# Logical_EPS_v_1_0.net
KiCad netlist of a schematic drawn in EAGLE
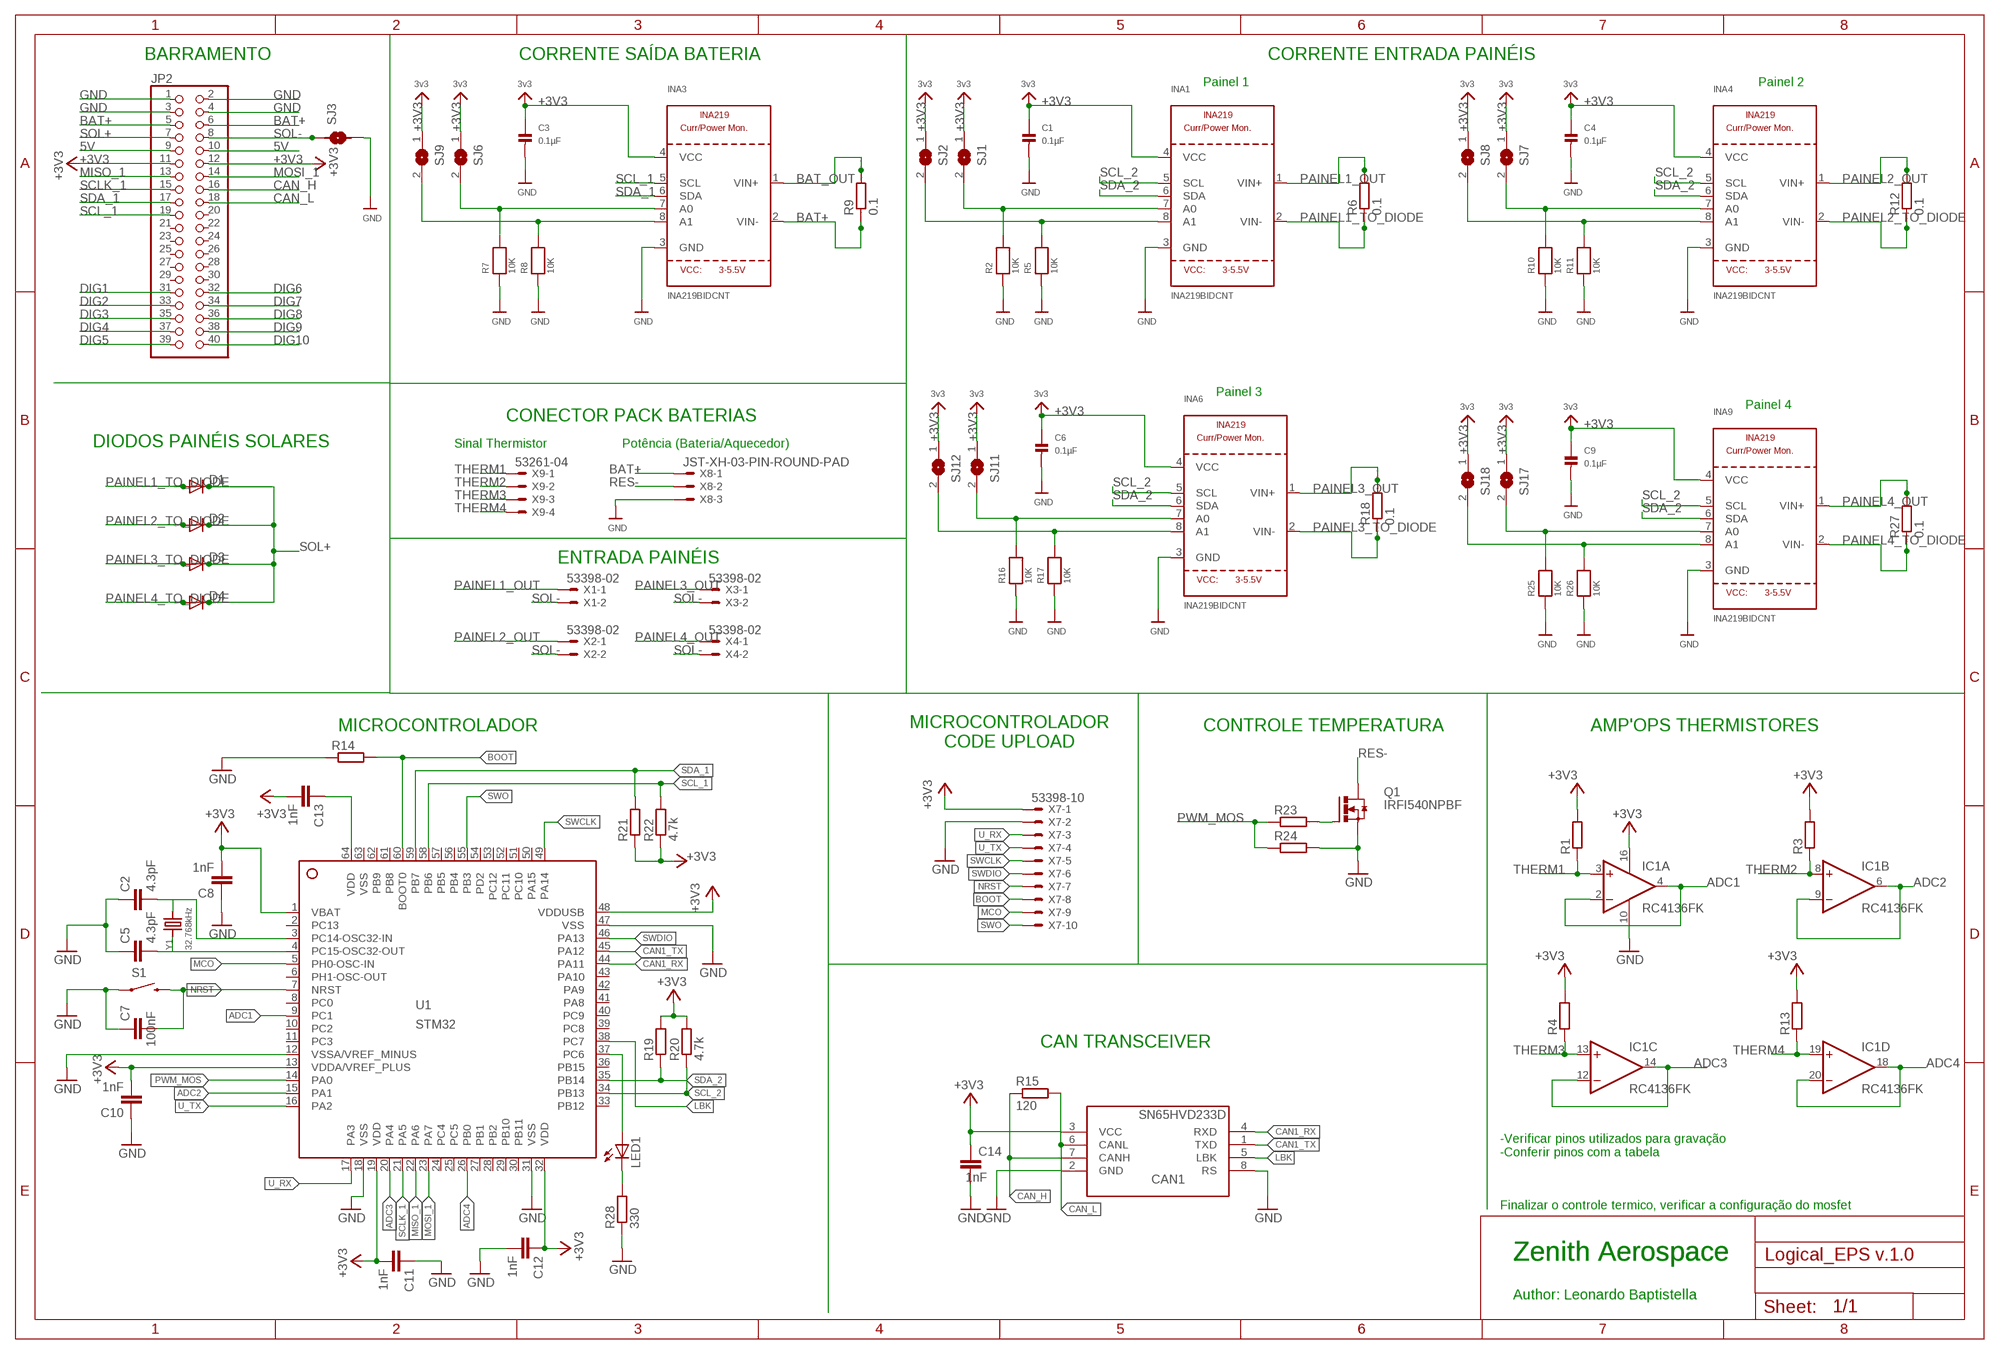
[diagram p0: schematic, sheet 1]

(export (version "E")
  (design (tool "Eeschema 10.0.6"))
  (components
    (comp (ref "C1")
      (value "0.1µF")
      (footprint "eagle-import:1206")
      (libsource (lib "eagle-import") (part "CAP_CERAMIC1206"))
    )
    (comp (ref "C2")
      (value "4.3pF")
      (footprint "eagle-import:C1206")
      (libsource (lib "eagle-import") (part "C-EUC1206"))
    )
    (comp (ref "C3")
      (value "0.1µF")
      (footprint "eagle-import:1206")
      (libsource (lib "eagle-import") (part "CAP_CERAMIC1206"))
    )
    (comp (ref "C4")
      (value "0.1µF")
      (footprint "eagle-import:1206")
      (libsource (lib "eagle-import") (part "CAP_CERAMIC1206"))
    )
    (comp (ref "C5")
      (value "4.3pF")
      (footprint "eagle-import:C1206")
      (libsource (lib "eagle-import") (part "C-EUC1206"))
    )
    (comp (ref "C6")
      (value "0.1µF")
      (footprint "eagle-import:1206")
      (libsource (lib "eagle-import") (part "CAP_CERAMIC1206"))
    )
    (comp (ref "C7")
      (value "100nF")
      (footprint "eagle-import:C1206")
      (libsource (lib "eagle-import") (part "C-EUC1206"))
    )
    (comp (ref "C8")
      (value "1nF")
      (footprint "eagle-import:C1206")
      (libsource (lib "eagle-import") (part "C-EUC1206"))
    )
    (comp (ref "C9")
      (value "0.1µF")
      (footprint "eagle-import:1206")
      (libsource (lib "eagle-import") (part "CAP_CERAMIC1206"))
    )
    (comp (ref "C10")
      (value "1nF")
      (footprint "eagle-import:C1206")
      (libsource (lib "eagle-import") (part "C-EUC1206"))
    )
    (comp (ref "C11")
      (value "1nF")
      (footprint "eagle-import:C1206")
      (libsource (lib "eagle-import") (part "C-EUC1206"))
    )
    (comp (ref "C12")
      (value "1nF")
      (footprint "eagle-import:C1206")
      (libsource (lib "eagle-import") (part "C-EUC1206"))
    )
    (comp (ref "C13")
      (value "1nF")
      (footprint "eagle-import:C1206")
      (libsource (lib "eagle-import") (part "C-EUC1206"))
    )
    (comp (ref "C14")
      (value "1nF")
      (footprint "eagle-import:C1206")
      (libsource (lib "eagle-import") (part "C-EUC1206"))
    )
    (comp (ref "CAN1")
      (value "SN65HVD233D")
      (footprint "eagle-import:SOIC8")
      (fields (field (name "MF") "Texas Instruments"))
      (libsource (lib "eagle-import") (part "SN65HVD233D"))
    )
    (comp (ref "D1")
      (value "DIODE-DO-214AC")
      (footprint "eagle-import:DO-214AC")
      (libsource (lib "eagle-import") (part "DIODE-DO-214AC"))
    )
    (comp (ref "D2")
      (value "DIODE-DO-214AC")
      (footprint "eagle-import:DO-214AC")
      (libsource (lib "eagle-import") (part "DIODE-DO-214AC"))
    )
    (comp (ref "D3")
      (value "DIODE-DO-214AC")
      (footprint "eagle-import:DO-214AC")
      (libsource (lib "eagle-import") (part "DIODE-DO-214AC"))
    )
    (comp (ref "D4")
      (value "DIODE-DO-214AC")
      (footprint "eagle-import:DO-214AC")
      (libsource (lib "eagle-import") (part "DIODE-DO-214AC"))
    )
    (comp (ref "IC1")
      (value "RC4136FK")
      (footprint "eagle-import:PLCC20S")
      (libsource (lib "eagle-import") (part "RC4136FK"))
    )
    (comp (ref "INA1")
      (value "INA219BIDCNT")
      (footprint "eagle-import:SOT23-8")
      (libsource (lib "eagle-import") (part "INA219"))
    )
    (comp (ref "INA3")
      (value "INA219BIDCNT")
      (footprint "eagle-import:SOT23-8")
      (libsource (lib "eagle-import") (part "INA219"))
    )
    (comp (ref "INA4")
      (value "INA219BIDCNT")
      (footprint "eagle-import:SOT23-8")
      (libsource (lib "eagle-import") (part "INA219"))
    )
    (comp (ref "INA6")
      (value "INA219BIDCNT")
      (footprint "eagle-import:SOT23-8")
      (libsource (lib "eagle-import") (part "INA219"))
    )
    (comp (ref "INA9")
      (value "INA219BIDCNT")
      (footprint "eagle-import:SOT23-8")
      (libsource (lib "eagle-import") (part "INA219"))
    )
    (comp (ref "JP2")
      (value "PINHD-2X20")
      (footprint "eagle-import:2X20")
      (libsource (lib "eagle-import") (part "PINHD-2X20"))
    )
    (comp (ref "LED1")
      (value "LEDSMT1206")
      (footprint "eagle-import:1206")
      (libsource (lib "eagle-import") (part "LEDSMT1206"))
    )
    (comp (ref "Q1")
      (value "IRFI540NPBF")
      (footprint "eagle-import:TO220BH")
      (libsource (lib "eagle-import") (part "IRFI540NPBF"))
    )
    (comp (ref "R1")
      (value "R-EU_R1206")
      (footprint "eagle-import:R1206")
      (libsource (lib "eagle-import") (part "R-EU_R1206"))
    )
    (comp (ref "R2")
      (value "10K")
      (footprint "eagle-import:1206")
      (libsource (lib "eagle-import") (part "RESISTOR1206"))
    )
    (comp (ref "R3")
      (value "R-EU_R1206")
      (footprint "eagle-import:R1206")
      (libsource (lib "eagle-import") (part "R-EU_R1206"))
    )
    (comp (ref "R4")
      (value "R-EU_R1206")
      (footprint "eagle-import:R1206")
      (libsource (lib "eagle-import") (part "R-EU_R1206"))
    )
    (comp (ref "R5")
      (value "10K")
      (footprint "eagle-import:1206")
      (libsource (lib "eagle-import") (part "RESISTOR1206"))
    )
    (comp (ref "R6")
      (value "0.1")
      (footprint "eagle-import:R2512")
      (libsource (lib "eagle-import") (part "RR2512"))
    )
    (comp (ref "R7")
      (value "10K")
      (footprint "eagle-import:1206")
      (libsource (lib "eagle-import") (part "RESISTOR1206"))
    )
    (comp (ref "R8")
      (value "10K")
      (footprint "eagle-import:1206")
      (libsource (lib "eagle-import") (part "RESISTOR1206"))
    )
    (comp (ref "R9")
      (value "0.1")
      (footprint "eagle-import:R2512")
      (libsource (lib "eagle-import") (part "RR2512"))
    )
    (comp (ref "R10")
      (value "10K")
      (footprint "eagle-import:1206")
      (libsource (lib "eagle-import") (part "RESISTOR1206"))
    )
    (comp (ref "R11")
      (value "10K")
      (footprint "eagle-import:1206")
      (libsource (lib "eagle-import") (part "RESISTOR1206"))
    )
    (comp (ref "R12")
      (value "0.1")
      (footprint "eagle-import:R2512")
      (libsource (lib "eagle-import") (part "RR2512"))
    )
    (comp (ref "R13")
      (value "R-EU_R1206")
      (footprint "eagle-import:R1206")
      (libsource (lib "eagle-import") (part "R-EU_R1206"))
    )
    (comp (ref "R14")
      (value "R-EU_R1206")
      (footprint "eagle-import:R1206")
      (libsource (lib "eagle-import") (part "R-EU_R1206"))
    )
    (comp (ref "R15")
      (value "120")
      (footprint "eagle-import:R1206")
      (libsource (lib "eagle-import") (part "R-EU_R1206"))
    )
    (comp (ref "R16")
      (value "10K")
      (footprint "eagle-import:1206")
      (libsource (lib "eagle-import") (part "RESISTOR1206"))
    )
    (comp (ref "R17")
      (value "10K")
      (footprint "eagle-import:1206")
      (libsource (lib "eagle-import") (part "RESISTOR1206"))
    )
    (comp (ref "R18")
      (value "0.1")
      (footprint "eagle-import:R2512")
      (libsource (lib "eagle-import") (part "RR2512"))
    )
    (comp (ref "R19")
      (value "4.7k")
      (footprint "eagle-import:R1206")
      (libsource (lib "eagle-import") (part "R-EU_R1206"))
    )
    (comp (ref "R20")
      (value "4.7k")
      (footprint "eagle-import:R1206")
      (libsource (lib "eagle-import") (part "R-EU_R1206"))
    )
    (comp (ref "R21")
      (value "4.7k")
      (footprint "eagle-import:R1206")
      (libsource (lib "eagle-import") (part "R-EU_R1206"))
    )
    (comp (ref "R22")
      (value "4.7k")
      (footprint "eagle-import:R1206")
      (libsource (lib "eagle-import") (part "R-EU_R1206"))
    )
    (comp (ref "R23")
      (value "R-EU_R1206")
      (footprint "eagle-import:R1206")
      (libsource (lib "eagle-import") (part "R-EU_R1206"))
    )
    (comp (ref "R24")
      (value "R-EU_R1206")
      (footprint "eagle-import:R1206")
      (libsource (lib "eagle-import") (part "R-EU_R1206"))
    )
    (comp (ref "R25")
      (value "10K")
      (footprint "eagle-import:1206")
      (libsource (lib "eagle-import") (part "RESISTOR1206"))
    )
    (comp (ref "R26")
      (value "10K")
      (footprint "eagle-import:1206")
      (libsource (lib "eagle-import") (part "RESISTOR1206"))
    )
    (comp (ref "R27")
      (value "0.1")
      (footprint "eagle-import:R2512")
      (libsource (lib "eagle-import") (part "RR2512"))
    )
    (comp (ref "R28")
      (value "330")
      (footprint "eagle-import:R1206")
      (libsource (lib "eagle-import") (part "R-EU_R1206"))
    )
    (comp (ref "S1")
      (value "SWITCH-MOMENTARY-2SMD-1101NE")
      (footprint "eagle-import:TACTILE-SWITCH-1101NE")
      (libsource (lib "eagle-import") (part "SWITCH-MOMENTARY-2SMD-1101NE"))
    )
    (comp (ref "SJ1")
      (value "SOLDERJUMPERREFLOW_NOPASTE")
      (footprint "eagle-import:SOLDERJUMPER_REFLOW_NOPASTE")
      (libsource (lib "eagle-import") (part "SOLDERJUMPERREFLOW_NOPASTE"))
    )
    (comp (ref "SJ2")
      (value "SOLDERJUMPERREFLOW_NOPASTE")
      (footprint "eagle-import:SOLDERJUMPER_REFLOW_NOPASTE")
      (libsource (lib "eagle-import") (part "SOLDERJUMPERREFLOW_NOPASTE"))
    )
    (comp (ref "SJ3")
      (value "SMD-JUMPER-2")
      (footprint "eagle-import:SMD-JUMPER-2")
      (libsource (lib "eagle-import") (part "SMD-JUMPER-2"))
    )
    (comp (ref "SJ6")
      (value "SOLDERJUMPERREFLOW_NOPASTE")
      (footprint "eagle-import:SOLDERJUMPER_REFLOW_NOPASTE")
      (libsource (lib "eagle-import") (part "SOLDERJUMPERREFLOW_NOPASTE"))
    )
    (comp (ref "SJ7")
      (value "SOLDERJUMPERREFLOW_NOPASTE")
      (footprint "eagle-import:SOLDERJUMPER_REFLOW_NOPASTE")
      (libsource (lib "eagle-import") (part "SOLDERJUMPERREFLOW_NOPASTE"))
    )
    (comp (ref "SJ8")
      (value "SOLDERJUMPERREFLOW_NOPASTE")
      (footprint "eagle-import:SOLDERJUMPER_REFLOW_NOPASTE")
      (libsource (lib "eagle-import") (part "SOLDERJUMPERREFLOW_NOPASTE"))
    )
    (comp (ref "SJ9")
      (value "SOLDERJUMPERREFLOW_NOPASTE")
      (footprint "eagle-import:SOLDERJUMPER_REFLOW_NOPASTE")
      (libsource (lib "eagle-import") (part "SOLDERJUMPERREFLOW_NOPASTE"))
    )
    (comp (ref "SJ11")
      (value "SOLDERJUMPERREFLOW_NOPASTE")
      (footprint "eagle-import:SOLDERJUMPER_REFLOW_NOPASTE")
      (libsource (lib "eagle-import") (part "SOLDERJUMPERREFLOW_NOPASTE"))
    )
    (comp (ref "SJ12")
      (value "SOLDERJUMPERREFLOW_NOPASTE")
      (footprint "eagle-import:SOLDERJUMPER_REFLOW_NOPASTE")
      (libsource (lib "eagle-import") (part "SOLDERJUMPERREFLOW_NOPASTE"))
    )
    (comp (ref "SJ17")
      (value "SOLDERJUMPERREFLOW_NOPASTE")
      (footprint "eagle-import:SOLDERJUMPER_REFLOW_NOPASTE")
      (libsource (lib "eagle-import") (part "SOLDERJUMPERREFLOW_NOPASTE"))
    )
    (comp (ref "SJ18")
      (value "SOLDERJUMPERREFLOW_NOPASTE")
      (footprint "eagle-import:SOLDERJUMPER_REFLOW_NOPASTE")
      (libsource (lib "eagle-import") (part "SOLDERJUMPERREFLOW_NOPASTE"))
    )
    (comp (ref "U1")
      (value "STM32")
      (footprint "eagle-import:LQFP64_10X10")
      (libsource (lib "eagle-import") (part "STM32L476RCT6"))
    )
    (comp (ref "X1")
      (value "53398-02")
      (footprint "eagle-import:53398-02")
      (fields (field (name "MF") "MOLEX"))
      (libsource (lib "eagle-import") (part "53?-02398"))
    )
    (comp (ref "X2")
      (value "53398-02")
      (footprint "eagle-import:53398-02")
      (fields (field (name "MF") "MOLEX"))
      (libsource (lib "eagle-import") (part "53?-02398"))
    )
    (comp (ref "X3")
      (value "53398-02")
      (footprint "eagle-import:53398-02")
      (fields (field (name "MF") "MOLEX"))
      (libsource (lib "eagle-import") (part "53?-02398"))
    )
    (comp (ref "X4")
      (value "53398-02")
      (footprint "eagle-import:53398-02")
      (fields (field (name "MF") "MOLEX"))
      (libsource (lib "eagle-import") (part "53?-02398"))
    )
    (comp (ref "X7")
      (value "53398-10")
      (footprint "eagle-import:53398-10")
      (fields (field (name "MF") "MOLEX") (field (name "MPN") "53398-1071"))
      (libsource (lib "eagle-import") (part "53?-10398"))
    )
    (comp (ref "X8")
      (value "JST-XH-03-PIN-ROUND-PAD")
      (footprint "eagle-import:JST-XH-03-PACKAGE-ROUND-PAD")
      (libsource (lib "eagle-import") (part "JST-XH-03-PIN-ROUND-PAD"))
    )
    (comp (ref "X9")
      (value "53261-04")
      (footprint "eagle-import:53261-04")
      (fields (field (name "MF") "MOLEX"))
      (libsource (lib "eagle-import") (part "53?-04261"))
    )
    (comp (ref "Y1")
      (value "32.768kHz")
      (footprint "eagle-import:CRYSTAL_8X3.8")
      (libsource (lib "eagle-import") (part "CRYSTAL8X3.8SMT"))
    )
  )
  (nets
    (net (code "1") (name "+3V3") (class "Default")
      (node (ref "C1") (pin "1") (pinfunction "P$1_1") (pintype "passive"))
      (node (ref "C10") (pin "2") (pinfunction "2_2") (pintype "passive"))
      (node (ref "C11") (pin "2") (pinfunction "2_2") (pintype "passive"))
      (node (ref "C12") (pin "1") (pinfunction "1_1") (pintype "passive"))
      (node (ref "C13") (pin "2") (pinfunction "2_2") (pintype "passive"))
      (node (ref "C14") (pin "1") (pinfunction "1_1") (pintype "passive"))
      (node (ref "C3") (pin "1") (pinfunction "P$1_1") (pintype "passive"))
      (node (ref "C4") (pin "1") (pinfunction "P$1_1") (pintype "passive"))
      (node (ref "C6") (pin "1") (pinfunction "P$1_1") (pintype "passive"))
      (node (ref "C8") (pin "2") (pinfunction "2_2") (pintype "passive"))
      (node (ref "C9") (pin "1") (pinfunction "P$1_1") (pintype "passive"))
      (node (ref "CAN1") (pin "3") (pinfunction "VCC_3") (pintype "power_in"))
      (node (ref "IC1") (pin "16") (pinfunction "V+_16") (pintype "power_in"))
      (node (ref "INA1") (pin "4") (pinfunction "VCC_4") (pintype "bidirectional"))
      (node (ref "INA3") (pin "4") (pinfunction "VCC_4") (pintype "bidirectional"))
      (node (ref "INA4") (pin "4") (pinfunction "VCC_4") (pintype "bidirectional"))
      (node (ref "INA6") (pin "4") (pinfunction "VCC_4") (pintype "bidirectional"))
      (node (ref "INA9") (pin "4") (pinfunction "VCC_4") (pintype "bidirectional"))
      (node (ref "JP2") (pin "11") (pinfunction "11_11") (pintype "passive"))
      (node (ref "JP2") (pin "12") (pinfunction "12_12") (pintype "passive"))
      (node (ref "R1") (pin "2") (pinfunction "2_2") (pintype "passive"))
      (node (ref "R13") (pin "2") (pinfunction "2_2") (pintype "passive"))
      (node (ref "R19") (pin "2") (pinfunction "2_2") (pintype "passive"))
      (node (ref "R20") (pin "2") (pinfunction "2_2") (pintype "passive"))
      (node (ref "R21") (pin "1") (pinfunction "1_1") (pintype "passive"))
      (node (ref "R22") (pin "1") (pinfunction "1_1") (pintype "passive"))
      (node (ref "R3") (pin "2") (pinfunction "2_2") (pintype "passive"))
      (node (ref "R4") (pin "2") (pinfunction "2_2") (pintype "passive"))
      (node (ref "SJ1") (pin "1") (pinfunction "1_1") (pintype "passive"))
      (node (ref "SJ11") (pin "1") (pinfunction "1_1") (pintype "passive"))
      (node (ref "SJ12") (pin "1") (pinfunction "1_1") (pintype "passive"))
      (node (ref "SJ17") (pin "1") (pinfunction "1_1") (pintype "passive"))
      (node (ref "SJ18") (pin "1") (pinfunction "1_1") (pintype "passive"))
      (node (ref "SJ2") (pin "1") (pinfunction "1_1") (pintype "passive"))
      (node (ref "SJ6") (pin "1") (pinfunction "1_1") (pintype "passive"))
      (node (ref "SJ7") (pin "1") (pinfunction "1_1") (pintype "passive"))
      (node (ref "SJ8") (pin "1") (pinfunction "1_1") (pintype "passive"))
      (node (ref "SJ9") (pin "1") (pinfunction "1_1") (pintype "passive"))
      (node (ref "U1") (pin "1") (pinfunction "VBAT_1") (pintype "passive"))
      (node (ref "U1") (pin "13") (pinfunction "VDDA/VREF_PLUS_13") (pintype "passive"))
      (node (ref "U1") (pin "19") (pinfunction "VDD_19") (pintype "power_in"))
      (node (ref "U1") (pin "32") (pinfunction "VDD_32") (pintype "power_in"))
      (node (ref "U1") (pin "48") (pinfunction "VDDUSB_48") (pintype "bidirectional"))
      (node (ref "X7") (pin "1") (pinfunction "S_1") (pintype "passive"))
    )
    (net (code "2") (name "/5V") (class "Default")
      (node (ref "JP2") (pin "10") (pinfunction "10_10") (pintype "passive"))
      (node (ref "JP2") (pin "9") (pinfunction "9_9") (pintype "passive"))
    )
    (net (code "3") (name "/BAT+") (class "Default")
      (node (ref "INA3") (pin "2") (pinfunction "VIN-_2") (pintype "bidirectional"))
      (node (ref "JP2") (pin "5") (pinfunction "5_5") (pintype "passive"))
      (node (ref "JP2") (pin "6") (pinfunction "6_6") (pintype "passive"))
      (node (ref "R9") (pin "1") (pinfunction "1_1") (pintype "passive"))
      (node (ref "X8") (pin "1") (pinfunction "S_1") (pintype "passive"))
    )
    (net (code "4") (name "/BAT_OUT") (class "Default")
      (node (ref "INA3") (pin "1") (pinfunction "VIN+_1") (pintype "bidirectional"))
      (node (ref "R9") (pin "2") (pinfunction "2_2") (pintype "passive"))
    )
    (net (code "5") (name "/DIG1") (class "Default")
      (node (ref "JP2") (pin "31") (pinfunction "31_31") (pintype "passive"))
    )
    (net (code "6") (name "/DIG2") (class "Default")
      (node (ref "JP2") (pin "33") (pinfunction "33_33") (pintype "passive"))
    )
    (net (code "7") (name "/DIG3") (class "Default")
      (node (ref "JP2") (pin "35") (pinfunction "35_35") (pintype "passive"))
    )
    (net (code "8") (name "/DIG4") (class "Default")
      (node (ref "JP2") (pin "37") (pinfunction "37_37") (pintype "passive"))
    )
    (net (code "9") (name "/DIG5") (class "Default")
      (node (ref "JP2") (pin "39") (pinfunction "39_39") (pintype "passive"))
    )
    (net (code "10") (name "/DIG6") (class "Default")
      (node (ref "JP2") (pin "32") (pinfunction "32_32") (pintype "passive"))
    )
    (net (code "11") (name "/DIG7") (class "Default")
      (node (ref "JP2") (pin "34") (pinfunction "34_34") (pintype "passive"))
    )
    (net (code "12") (name "/DIG8") (class "Default")
      (node (ref "JP2") (pin "36") (pinfunction "36_36") (pintype "passive"))
    )
    (net (code "13") (name "/DIG9") (class "Default")
      (node (ref "JP2") (pin "38") (pinfunction "38_38") (pintype "passive"))
    )
    (net (code "14") (name "/DIG10") (class "Default")
      (node (ref "JP2") (pin "40") (pinfunction "40_40") (pintype "passive"))
    )
    (net (code "15") (name "/PAINEL1_OUT") (class "Default")
      (node (ref "INA1") (pin "1") (pinfunction "VIN+_1") (pintype "bidirectional"))
      (node (ref "R6") (pin "2") (pinfunction "2_2") (pintype "passive"))
      (node (ref "X1") (pin "1") (pinfunction "S_1") (pintype "passive"))
    )
    (net (code "16") (name "/PAINEL1_TO_DIODE") (class "Default")
      (node (ref "D1") (pin "A") (pinfunction "A_A") (pintype "passive"))
      (node (ref "INA1") (pin "2") (pinfunction "VIN-_2") (pintype "bidirectional"))
      (node (ref "R6") (pin "1") (pinfunction "1_1") (pintype "passive"))
    )
    (net (code "17") (name "/PAINEL2_OUT") (class "Default")
      (node (ref "INA4") (pin "1") (pinfunction "VIN+_1") (pintype "bidirectional"))
      (node (ref "R12") (pin "2") (pinfunction "2_2") (pintype "passive"))
      (node (ref "X2") (pin "1") (pinfunction "S_1") (pintype "passive"))
    )
    (net (code "18") (name "/PAINEL2_TO_DIODE") (class "Default")
      (node (ref "D2") (pin "A") (pinfunction "A_A") (pintype "passive"))
      (node (ref "INA4") (pin "2") (pinfunction "VIN-_2") (pintype "bidirectional"))
      (node (ref "R12") (pin "1") (pinfunction "1_1") (pintype "passive"))
    )
    (net (code "19") (name "/PAINEL3_OUT") (class "Default")
      (node (ref "INA6") (pin "1") (pinfunction "VIN+_1") (pintype "bidirectional"))
      (node (ref "R18") (pin "2") (pinfunction "2_2") (pintype "passive"))
      (node (ref "X3") (pin "1") (pinfunction "S_1") (pintype "passive"))
    )
    (net (code "20") (name "/PAINEL3_TO_DIODE") (class "Default")
      (node (ref "D3") (pin "A") (pinfunction "A_A") (pintype "passive"))
      (node (ref "INA6") (pin "2") (pinfunction "VIN-_2") (pintype "bidirectional"))
      (node (ref "R18") (pin "1") (pinfunction "1_1") (pintype "passive"))
    )
    (net (code "21") (name "/PAINEL4_OUT") (class "Default")
      (node (ref "INA9") (pin "1") (pinfunction "VIN+_1") (pintype "bidirectional"))
      (node (ref "R27") (pin "2") (pinfunction "2_2") (pintype "passive"))
      (node (ref "X4") (pin "1") (pinfunction "S_1") (pintype "passive"))
    )
    (net (code "22") (name "/PAINEL4_TO_DIODE") (class "Default")
      (node (ref "D4") (pin "A") (pinfunction "A_A") (pintype "passive"))
      (node (ref "INA9") (pin "2") (pinfunction "VIN-_2") (pintype "bidirectional"))
      (node (ref "R27") (pin "1") (pinfunction "1_1") (pintype "passive"))
    )
    (net (code "23") (name "/RES-") (class "Default")
      (node (ref "Q1") (pin "D") (pinfunction "D_D") (pintype "passive"))
      (node (ref "X8") (pin "2") (pinfunction "S_2") (pintype "passive"))
    )
    (net (code "24") (name "/SOL+") (class "Default")
      (node (ref "D1") (pin "C") (pinfunction "C_C") (pintype "passive"))
      (node (ref "D2") (pin "C") (pinfunction "C_C") (pintype "passive"))
      (node (ref "D3") (pin "C") (pinfunction "C_C") (pintype "passive"))
      (node (ref "D4") (pin "C") (pinfunction "C_C") (pintype "passive"))
      (node (ref "JP2") (pin "7") (pinfunction "7_7") (pintype "passive"))
    )
    (net (code "25") (name "/SOL-") (class "Default")
      (node (ref "JP2") (pin "8") (pinfunction "8_8") (pintype "passive"))
      (node (ref "SJ3") (pin "1") (pinfunction "1_1") (pintype "passive"))
      (node (ref "X1") (pin "2") (pinfunction "S_2") (pintype "passive"))
      (node (ref "X2") (pin "2") (pinfunction "S_2") (pintype "passive"))
      (node (ref "X3") (pin "2") (pinfunction "S_2") (pintype "passive"))
      (node (ref "X4") (pin "2") (pinfunction "S_2") (pintype "passive"))
    )
    (net (code "26") (name "/THERM1") (class "Default")
      (node (ref "IC1") (pin "3") (pinfunction "+IN_3") (pintype "input"))
      (node (ref "R1") (pin "1") (pinfunction "1_1") (pintype "passive"))
      (node (ref "X9") (pin "1") (pinfunction "S_1") (pintype "passive"))
    )
    (net (code "27") (name "/THERM2") (class "Default")
      (node (ref "IC1") (pin "8") (pinfunction "+IN_8") (pintype "input"))
      (node (ref "R3") (pin "1") (pinfunction "1_1") (pintype "passive"))
      (node (ref "X9") (pin "2") (pinfunction "S_2") (pintype "passive"))
    )
    (net (code "28") (name "/THERM3") (class "Default")
      (node (ref "IC1") (pin "13") (pinfunction "+IN_13") (pintype "input"))
      (node (ref "R4") (pin "1") (pinfunction "1_1") (pintype "passive"))
      (node (ref "X9") (pin "3") (pinfunction "S_3") (pintype "passive"))
    )
    (net (code "29") (name "/THERM4") (class "Default")
      (node (ref "IC1") (pin "19") (pinfunction "+IN_19") (pintype "input"))
      (node (ref "R13") (pin "1") (pinfunction "1_1") (pintype "passive"))
      (node (ref "X9") (pin "4") (pinfunction "S_4") (pintype "passive"))
    )
    (net (code "30") (name "/VSS") (class "Default")
      (node (ref "U1") (pin "63") (pinfunction "VSS_63") (pintype "power_in"))
    )
    (net (code "31") (name "ADC1") (class "Default")
      (node (ref "IC1") (pin "2") (pinfunction "-IN_2") (pintype "input"))
      (node (ref "IC1") (pin "4") (pinfunction "OUT_4") (pintype "output"))
      (node (ref "U1") (pin "9") (pinfunction "PC1_9") (pintype "bidirectional"))
    )
    (net (code "32") (name "ADC2") (class "Default")
      (node (ref "IC1") (pin "6") (pinfunction "OUT_6") (pintype "output"))
      (node (ref "IC1") (pin "9") (pinfunction "-IN_9") (pintype "input"))
      (node (ref "U1") (pin "15") (pinfunction "PA1_15") (pintype "bidirectional"))
    )
    (net (code "33") (name "ADC3") (class "Default")
      (node (ref "IC1") (pin "12") (pinfunction "-IN_12") (pintype "input"))
      (node (ref "IC1") (pin "14") (pinfunction "OUT_14") (pintype "output"))
      (node (ref "U1") (pin "20") (pinfunction "PA4_20") (pintype "bidirectional"))
    )
    (net (code "34") (name "ADC4") (class "Default")
      (node (ref "IC1") (pin "18") (pinfunction "OUT_18") (pintype "output"))
      (node (ref "IC1") (pin "20") (pinfunction "-IN_20") (pintype "input"))
      (node (ref "U1") (pin "26") (pinfunction "PB0_26") (pintype "bidirectional"))
    )
    (net (code "35") (name "BOOT") (class "Default")
      (node (ref "R14") (pin "2") (pinfunction "2_2") (pintype "passive"))
      (node (ref "U1") (pin "60") (pinfunction "BOOT0_60") (pintype "input"))
      (node (ref "X7") (pin "8") (pinfunction "S_8") (pintype "passive"))
    )
    (net (code "36") (name "CAN1_RX") (class "Default")
      (node (ref "CAN1") (pin "4") (pinfunction "RXD_4") (pintype "output"))
      (node (ref "U1") (pin "44") (pinfunction "PA11_44") (pintype "bidirectional"))
    )
    (net (code "37") (name "CAN1_TX") (class "Default")
      (node (ref "CAN1") (pin "1") (pinfunction "TXD_1") (pintype "bidirectional"))
      (node (ref "U1") (pin "45") (pinfunction "PA12_45") (pintype "bidirectional"))
    )
    (net (code "38") (name "CAN_H") (class "Default")
      (node (ref "CAN1") (pin "7") (pinfunction "CANH_7") (pintype "bidirectional"))
      (node (ref "JP2") (pin "16") (pinfunction "16_16") (pintype "passive"))
      (node (ref "R15") (pin "1") (pinfunction "1_1") (pintype "passive"))
    )
    (net (code "39") (name "CAN_L") (class "Default")
      (node (ref "CAN1") (pin "6") (pinfunction "CANL_6") (pintype "bidirectional"))
      (node (ref "JP2") (pin "18") (pinfunction "18_18") (pintype "passive"))
      (node (ref "R15") (pin "2") (pinfunction "2_2") (pintype "passive"))
    )
    (net (code "40") (name "GND") (class "Default")
      (node (ref "C1") (pin "2") (pinfunction "P$2_2") (pintype "passive"))
      (node (ref "C10") (pin "1") (pinfunction "1_1") (pintype "passive"))
      (node (ref "C11") (pin "1") (pinfunction "1_1") (pintype "passive"))
      (node (ref "C12") (pin "2") (pinfunction "2_2") (pintype "passive"))
      (node (ref "C14") (pin "2") (pinfunction "2_2") (pintype "passive"))
      (node (ref "C2") (pin "1") (pinfunction "1_1") (pintype "passive"))
      (node (ref "C3") (pin "2") (pinfunction "P$2_2") (pintype "passive"))
      (node (ref "C4") (pin "2") (pinfunction "P$2_2") (pintype "passive"))
      (node (ref "C5") (pin "1") (pinfunction "1_1") (pintype "passive"))
      (node (ref "C6") (pin "2") (pinfunction "P$2_2") (pintype "passive"))
      (node (ref "C7") (pin "1") (pinfunction "1_1") (pintype "passive"))
      (node (ref "C8") (pin "1") (pinfunction "1_1") (pintype "passive"))
      (node (ref "C9") (pin "2") (pinfunction "P$2_2") (pintype "passive"))
      (node (ref "CAN1") (pin "2") (pinfunction "GND_2") (pintype "power_in"))
      (node (ref "CAN1") (pin "8") (pinfunction "RS_8") (pintype "input"))
      (node (ref "IC1") (pin "10") (pinfunction "V-_10") (pintype "power_in"))
      (node (ref "INA1") (pin "3") (pinfunction "GND_3") (pintype "bidirectional"))
      (node (ref "INA3") (pin "3") (pinfunction "GND_3") (pintype "bidirectional"))
      (node (ref "INA4") (pin "3") (pinfunction "GND_3") (pintype "bidirectional"))
      (node (ref "INA6") (pin "3") (pinfunction "GND_3") (pintype "bidirectional"))
      (node (ref "INA9") (pin "3") (pinfunction "GND_3") (pintype "bidirectional"))
      (node (ref "JP2") (pin "1") (pinfunction "1_1") (pintype "passive"))
      (node (ref "JP2") (pin "2") (pinfunction "2_2") (pintype "passive"))
      (node (ref "JP2") (pin "3") (pinfunction "3_3") (pintype "passive"))
      (node (ref "JP2") (pin "4") (pinfunction "4_4") (pintype "passive"))
      (node (ref "Q1") (pin "S") (pinfunction "S_S") (pintype "passive"))
      (node (ref "R10") (pin "1") (pinfunction "1_1") (pintype "passive"))
      (node (ref "R11") (pin "1") (pinfunction "1_1") (pintype "passive"))
      (node (ref "R14") (pin "1") (pinfunction "1_1") (pintype "passive"))
      (node (ref "R16") (pin "1") (pinfunction "1_1") (pintype "passive"))
      (node (ref "R17") (pin "1") (pinfunction "1_1") (pintype "passive"))
      (node (ref "R2") (pin "1") (pinfunction "1_1") (pintype "passive"))
      (node (ref "R24") (pin "2") (pinfunction "2_2") (pintype "passive"))
      (node (ref "R25") (pin "1") (pinfunction "1_1") (pintype "passive"))
      (node (ref "R26") (pin "1") (pinfunction "1_1") (pintype "passive"))
      (node (ref "R28") (pin "1") (pinfunction "1_1") (pintype "passive"))
      (node (ref "R5") (pin "1") (pinfunction "1_1") (pintype "passive"))
      (node (ref "R7") (pin "1") (pinfunction "1_1") (pintype "passive"))
      (node (ref "R8") (pin "1") (pinfunction "1_1") (pintype "passive"))
      (node (ref "S1") (pin "1") (pinfunction "1_1") (pintype "passive"))
      (node (ref "SJ3") (pin "2") (pinfunction "2_2") (pintype "passive"))
      (node (ref "U1") (pin "12") (pinfunction "VSSA/VREF_MINUS_12") (pintype "passive"))
      (node (ref "U1") (pin "18") (pinfunction "VSS_18") (pintype "power_in"))
      (node (ref "U1") (pin "31") (pinfunction "VSS_31") (pintype "power_in"))
      (node (ref "U1") (pin "47") (pinfunction "VSS_47") (pintype "power_in"))
      (node (ref "X7") (pin "2") (pinfunction "S_2") (pintype "passive"))
      (node (ref "X8") (pin "3") (pinfunction "S_3") (pintype "passive"))
    )
    (net (code "41") (name "LBK") (class "Default")
      (node (ref "CAN1") (pin "5") (pinfunction "LBK_5") (pintype "output"))
      (node (ref "U1") (pin "38") (pinfunction "PC7_38") (pintype "bidirectional"))
    )
    (net (code "42") (name "MCO") (class "Default")
      (node (ref "U1") (pin "5") (pinfunction "PH0-OSC-IN_5") (pintype "bidirectional"))
      (node (ref "X7") (pin "9") (pinfunction "S_9") (pintype "passive"))
    )
    (net (code "43") (name "MISO_1") (class "Default")
      (node (ref "JP2") (pin "13") (pinfunction "13_13") (pintype "passive"))
      (node (ref "U1") (pin "22") (pinfunction "PA6_22") (pintype "bidirectional"))
    )
    (net (code "44") (name "MOSI_1") (class "Default")
      (node (ref "JP2") (pin "14") (pinfunction "14_14") (pintype "passive"))
      (node (ref "U1") (pin "23") (pinfunction "PA7_23") (pintype "bidirectional"))
    )
    (net (code "45") (name "NRST") (class "Default")
      (node (ref "C7") (pin "2") (pinfunction "2_2") (pintype "passive"))
      (node (ref "S1") (pin "2") (pinfunction "2_2") (pintype "passive"))
      (node (ref "U1") (pin "7") (pinfunction "NRST_7") (pintype "input"))
      (node (ref "X7") (pin "7") (pinfunction "S_7") (pintype "passive"))
    )
    (net (code "46") (name "Net-(C13-Pad1)") (class "Default")
      (node (ref "C13") (pin "1") (pinfunction "1_1") (pintype "passive"))
      (node (ref "U1") (pin "64") (pinfunction "VDD_64") (pintype "power_in"))
    )
    (net (code "47") (name "Net-(INA1-A0)") (class "Default")
      (node (ref "INA1") (pin "7") (pinfunction "A0_7") (pintype "bidirectional"))
      (node (ref "R2") (pin "2") (pinfunction "2_2") (pintype "passive"))
      (node (ref "SJ1") (pin "2") (pinfunction "2_2") (pintype "passive"))
    )
    (net (code "48") (name "Net-(INA1-A1)") (class "Default")
      (node (ref "INA1") (pin "8") (pinfunction "A1_8") (pintype "bidirectional"))
      (node (ref "R5") (pin "2") (pinfunction "2_2") (pintype "passive"))
      (node (ref "SJ2") (pin "2") (pinfunction "2_2") (pintype "passive"))
    )
    (net (code "49") (name "Net-(INA3-A0)") (class "Default")
      (node (ref "INA3") (pin "7") (pinfunction "A0_7") (pintype "bidirectional"))
      (node (ref "R7") (pin "2") (pinfunction "2_2") (pintype "passive"))
      (node (ref "SJ6") (pin "2") (pinfunction "2_2") (pintype "passive"))
    )
    (net (code "50") (name "Net-(INA3-A1)") (class "Default")
      (node (ref "INA3") (pin "8") (pinfunction "A1_8") (pintype "bidirectional"))
      (node (ref "R8") (pin "2") (pinfunction "2_2") (pintype "passive"))
      (node (ref "SJ9") (pin "2") (pinfunction "2_2") (pintype "passive"))
    )
    (net (code "51") (name "Net-(INA4-A0)") (class "Default")
      (node (ref "INA4") (pin "7") (pinfunction "A0_7") (pintype "bidirectional"))
      (node (ref "R10") (pin "2") (pinfunction "2_2") (pintype "passive"))
      (node (ref "SJ7") (pin "2") (pinfunction "2_2") (pintype "passive"))
    )
    (net (code "52") (name "Net-(INA4-A1)") (class "Default")
      (node (ref "INA4") (pin "8") (pinfunction "A1_8") (pintype "bidirectional"))
      (node (ref "R11") (pin "2") (pinfunction "2_2") (pintype "passive"))
      (node (ref "SJ8") (pin "2") (pinfunction "2_2") (pintype "passive"))
    )
    (net (code "53") (name "Net-(INA6-A0)") (class "Default")
      (node (ref "INA6") (pin "7") (pinfunction "A0_7") (pintype "bidirectional"))
      (node (ref "R16") (pin "2") (pinfunction "2_2") (pintype "passive"))
      (node (ref "SJ11") (pin "2") (pinfunction "2_2") (pintype "passive"))
    )
    (net (code "54") (name "Net-(INA6-A1)") (class "Default")
      (node (ref "INA6") (pin "8") (pinfunction "A1_8") (pintype "bidirectional"))
      (node (ref "R17") (pin "2") (pinfunction "2_2") (pintype "passive"))
      (node (ref "SJ12") (pin "2") (pinfunction "2_2") (pintype "passive"))
    )
    (net (code "55") (name "Net-(INA9-A0)") (class "Default")
      (node (ref "INA9") (pin "7") (pinfunction "A0_7") (pintype "bidirectional"))
      (node (ref "R25") (pin "2") (pinfunction "2_2") (pintype "passive"))
      (node (ref "SJ17") (pin "2") (pinfunction "2_2") (pintype "passive"))
    )
    (net (code "56") (name "Net-(INA9-A1)") (class "Default")
      (node (ref "INA9") (pin "8") (pinfunction "A1_8") (pintype "bidirectional"))
      (node (ref "R26") (pin "2") (pinfunction "2_2") (pintype "passive"))
      (node (ref "SJ18") (pin "2") (pinfunction "2_2") (pintype "passive"))
    )
    (net (code "57") (name "Net-(LED1-PadC)") (class "Default")
      (node (ref "LED1") (pin "C") (pinfunction "C_C") (pintype "passive"))
      (node (ref "R28") (pin "2") (pinfunction "2_2") (pintype "passive"))
    )
    (net (code "58") (name "Net-(Q1-PadG)") (class "Default")
      (node (ref "Q1") (pin "G") (pinfunction "G_G") (pintype "passive"))
      (node (ref "R23") (pin "2") (pinfunction "2_2") (pintype "passive"))
    )
    (net (code "59") (name "Net-(U1-PC6)") (class "Default")
      (node (ref "LED1") (pin "A") (pinfunction "A_A") (pintype "passive"))
      (node (ref "U1") (pin "37") (pinfunction "PC6_37") (pintype "bidirectional"))
    )
    (net (code "60") (name "Net-(U1-PC14-OSC32-IN)") (class "Default")
      (node (ref "C2") (pin "2") (pinfunction "2_2") (pintype "passive"))
      (node (ref "U1") (pin "3") (pinfunction "PC14-OSC32-IN_3") (pintype "bidirectional"))
      (node (ref "Y1") (pin "P$4") (pinfunction "2_P$4") (pintype "passive"))
    )
    (net (code "61") (name "Net-(U1-PC15-OSC32-OUT)") (class "Default")
      (node (ref "C5") (pin "2") (pinfunction "2_2") (pintype "passive"))
      (node (ref "U1") (pin "4") (pinfunction "PC15-OSC32-OUT_4") (pintype "bidirectional"))
      (node (ref "Y1") (pin "P$1") (pinfunction "1_P$1") (pintype "passive"))
    )
    (net (code "62") (name "PWM_MOS") (class "Default")
      (node (ref "R23") (pin "1") (pinfunction "1_1") (pintype "passive"))
      (node (ref "R24") (pin "1") (pinfunction "1_1") (pintype "passive"))
      (node (ref "U1") (pin "14") (pinfunction "PA0_14") (pintype "bidirectional"))
    )
    (net (code "63") (name "SCLK_1") (class "Default")
      (node (ref "JP2") (pin "15") (pinfunction "15_15") (pintype "passive"))
      (node (ref "U1") (pin "21") (pinfunction "PA5_21") (pintype "bidirectional"))
    )
    (net (code "64") (name "SCL_1") (class "Default")
      (node (ref "INA3") (pin "5") (pinfunction "SCL_5") (pintype "bidirectional"))
      (node (ref "JP2") (pin "19") (pinfunction "19_19") (pintype "passive"))
      (node (ref "R22") (pin "2") (pinfunction "2_2") (pintype "passive"))
      (node (ref "U1") (pin "58") (pinfunction "PB6_58") (pintype "bidirectional"))
    )
    (net (code "65") (name "SCL_2") (class "Default")
      (node (ref "INA1") (pin "5") (pinfunction "SCL_5") (pintype "bidirectional"))
      (node (ref "INA4") (pin "5") (pinfunction "SCL_5") (pintype "bidirectional"))
      (node (ref "INA6") (pin "5") (pinfunction "SCL_5") (pintype "bidirectional"))
      (node (ref "INA9") (pin "5") (pinfunction "SCL_5") (pintype "bidirectional"))
      (node (ref "R20") (pin "1") (pinfunction "1_1") (pintype "passive"))
      (node (ref "U1") (pin "34") (pinfunction "PB13_34") (pintype "bidirectional"))
    )
    (net (code "66") (name "SDA_1") (class "Default")
      (node (ref "INA3") (pin "6") (pinfunction "SDA_6") (pintype "bidirectional"))
      (node (ref "JP2") (pin "17") (pinfunction "17_17") (pintype "passive"))
      (node (ref "R21") (pin "2") (pinfunction "2_2") (pintype "passive"))
      (node (ref "U1") (pin "59") (pinfunction "PB7_59") (pintype "bidirectional"))
    )
    (net (code "67") (name "SDA_2") (class "Default")
      (node (ref "INA1") (pin "6") (pinfunction "SDA_6") (pintype "bidirectional"))
      (node (ref "INA4") (pin "6") (pinfunction "SDA_6") (pintype "bidirectional"))
      (node (ref "INA6") (pin "6") (pinfunction "SDA_6") (pintype "bidirectional"))
      (node (ref "INA9") (pin "6") (pinfunction "SDA_6") (pintype "bidirectional"))
      (node (ref "R19") (pin "1") (pinfunction "1_1") (pintype "passive"))
      (node (ref "U1") (pin "35") (pinfunction "PB14_35") (pintype "bidirectional"))
    )
    (net (code "68") (name "SWCLK") (class "Default")
      (node (ref "U1") (pin "49") (pinfunction "PA14_49") (pintype "input"))
      (node (ref "X7") (pin "5") (pinfunction "S_5") (pintype "passive"))
    )
    (net (code "69") (name "SWDIO") (class "Default")
      (node (ref "U1") (pin "46") (pinfunction "PA13_46") (pintype "input"))
      (node (ref "X7") (pin "6") (pinfunction "S_6") (pintype "passive"))
    )
    (net (code "70") (name "SWO") (class "Default")
      (node (ref "U1") (pin "55") (pinfunction "PB3_55") (pintype "output"))
      (node (ref "X7") (pin "10") (pinfunction "S_10") (pintype "passive"))
    )
    (net (code "71") (name "U_RX") (class "Default")
      (node (ref "U1") (pin "17") (pinfunction "PA3_17") (pintype "bidirectional"))
      (node (ref "X7") (pin "3") (pinfunction "S_3") (pintype "passive"))
    )
    (net (code "72") (name "U_TX") (class "Default")
      (node (ref "U1") (pin "16") (pinfunction "PA2_16") (pintype "bidirectional"))
      (node (ref "X7") (pin "4") (pinfunction "S_4") (pintype "passive"))
    )
    (net (code "73") (name "unconnected-(JP2-Pad20)") (class "Default")
      (node (ref "JP2") (pin "20") (pinfunction "20_20") (pintype "passive"))
    )
    (net (code "74") (name "unconnected-(JP2-Pad21)") (class "Default")
      (node (ref "JP2") (pin "21") (pinfunction "21_21") (pintype "passive"))
    )
    (net (code "75") (name "unconnected-(JP2-Pad22)") (class "Default")
      (node (ref "JP2") (pin "22") (pinfunction "22_22") (pintype "passive"))
    )
    (net (code "76") (name "unconnected-(JP2-Pad23)") (class "Default")
      (node (ref "JP2") (pin "23") (pinfunction "23_23") (pintype "passive"))
    )
    (net (code "77") (name "unconnected-(JP2-Pad24)") (class "Default")
      (node (ref "JP2") (pin "24") (pinfunction "24_24") (pintype "passive"))
    )
    (net (code "78") (name "unconnected-(JP2-Pad25)") (class "Default")
      (node (ref "JP2") (pin "25") (pinfunction "25_25") (pintype "passive"))
    )
    (net (code "79") (name "unconnected-(JP2-Pad26)") (class "Default")
      (node (ref "JP2") (pin "26") (pinfunction "26_26") (pintype "passive"))
    )
    (net (code "80") (name "unconnected-(JP2-Pad27)") (class "Default")
      (node (ref "JP2") (pin "27") (pinfunction "27_27") (pintype "passive"))
    )
    (net (code "81") (name "unconnected-(JP2-Pad28)") (class "Default")
      (node (ref "JP2") (pin "28") (pinfunction "28_28") (pintype "passive"))
    )
    (net (code "82") (name "unconnected-(JP2-Pad29)") (class "Default")
      (node (ref "JP2") (pin "29") (pinfunction "29_29") (pintype "passive"))
    )
    (net (code "83") (name "unconnected-(JP2-Pad30)") (class "Default")
      (node (ref "JP2") (pin "30") (pinfunction "30_30") (pintype "passive"))
    )
    (net (code "84") (name "unconnected-(U1-PA8-Pad41)") (class "Default")
      (node (ref "U1") (pin "41") (pinfunction "PA8_41") (pintype "bidirectional"))
    )
    (net (code "85") (name "unconnected-(U1-PA9-Pad42)") (class "Default")
      (node (ref "U1") (pin "42") (pinfunction "PA9_42") (pintype "bidirectional"))
    )
    (net (code "86") (name "unconnected-(U1-PA10-Pad43)") (class "Default")
      (node (ref "U1") (pin "43") (pinfunction "PA10_43") (pintype "bidirectional"))
    )
    (net (code "87") (name "unconnected-(U1-PA15-Pad50)") (class "Default")
      (node (ref "U1") (pin "50") (pinfunction "PA15_50") (pintype "input"))
    )
    (net (code "88") (name "unconnected-(U1-PB1-Pad27)") (class "Default")
      (node (ref "U1") (pin "27") (pinfunction "PB1_27") (pintype "bidirectional"))
    )
    (net (code "89") (name "unconnected-(U1-PB2-Pad28)") (class "Default")
      (node (ref "U1") (pin "28") (pinfunction "PB2_28") (pintype "bidirectional"))
    )
    (net (code "90") (name "unconnected-(U1-PB4-Pad56)") (class "Default")
      (node (ref "U1") (pin "56") (pinfunction "PB4_56") (pintype "input"))
    )
    (net (code "91") (name "unconnected-(U1-PB5-Pad57)") (class "Default")
      (node (ref "U1") (pin "57") (pinfunction "PB5_57") (pintype "bidirectional"))
    )
    (net (code "92") (name "unconnected-(U1-PB8-Pad61)") (class "Default")
      (node (ref "U1") (pin "61") (pinfunction "PB8_61") (pintype "bidirectional"))
    )
    (net (code "93") (name "unconnected-(U1-PB9-Pad62)") (class "Default")
      (node (ref "U1") (pin "62") (pinfunction "PB9_62") (pintype "bidirectional"))
    )
    (net (code "94") (name "unconnected-(U1-PB10-Pad29)") (class "Default")
      (node (ref "U1") (pin "29") (pinfunction "PB10_29") (pintype "bidirectional"))
    )
    (net (code "95") (name "unconnected-(U1-PB11-Pad30)") (class "Default")
      (node (ref "U1") (pin "30") (pinfunction "PB11_30") (pintype "bidirectional"))
    )
    (net (code "96") (name "unconnected-(U1-PB12-Pad33)") (class "Default")
      (node (ref "U1") (pin "33") (pinfunction "PB12_33") (pintype "bidirectional"))
    )
    (net (code "97") (name "unconnected-(U1-PB15-Pad36)") (class "Default")
      (node (ref "U1") (pin "36") (pinfunction "PB15_36") (pintype "bidirectional"))
    )
    (net (code "98") (name "unconnected-(U1-PC0-Pad8)") (class "Default")
      (node (ref "U1") (pin "8") (pinfunction "PC0_8") (pintype "bidirectional"))
    )
    (net (code "99") (name "unconnected-(U1-PC2-Pad10)") (class "Default")
      (node (ref "U1") (pin "10") (pinfunction "PC2_10") (pintype "bidirectional"))
    )
    (net (code "100") (name "unconnected-(U1-PC3-Pad11)") (class "Default")
      (node (ref "U1") (pin "11") (pinfunction "PC3_11") (pintype "bidirectional"))
    )
    (net (code "101") (name "unconnected-(U1-PC4-Pad24)") (class "Default")
      (node (ref "U1") (pin "24") (pinfunction "PC4_24") (pintype "bidirectional"))
    )
    (net (code "102") (name "unconnected-(U1-PC5-Pad25)") (class "Default")
      (node (ref "U1") (pin "25") (pinfunction "PC5_25") (pintype "bidirectional"))
    )
    (net (code "103") (name "unconnected-(U1-PC8-Pad39)") (class "Default")
      (node (ref "U1") (pin "39") (pinfunction "PC8_39") (pintype "bidirectional"))
    )
    (net (code "104") (name "unconnected-(U1-PC9-Pad40)") (class "Default")
      (node (ref "U1") (pin "40") (pinfunction "PC9_40") (pintype "bidirectional"))
    )
    (net (code "105") (name "unconnected-(U1-PC10-Pad51)") (class "Default")
      (node (ref "U1") (pin "51") (pinfunction "PC10_51") (pintype "bidirectional"))
    )
    (net (code "106") (name "unconnected-(U1-PC11-Pad52)") (class "Default")
      (node (ref "U1") (pin "52") (pinfunction "PC11_52") (pintype "bidirectional"))
    )
    (net (code "107") (name "unconnected-(U1-PC12-Pad53)") (class "Default")
      (node (ref "U1") (pin "53") (pinfunction "PC12_53") (pintype "bidirectional"))
    )
    (net (code "108") (name "unconnected-(U1-PC13-Pad2)") (class "Default")
      (node (ref "U1") (pin "2") (pinfunction "PC13_2") (pintype "bidirectional"))
    )
    (net (code "109") (name "unconnected-(U1-PD2-Pad54)") (class "Default")
      (node (ref "U1") (pin "54") (pinfunction "PD2_54") (pintype "bidirectional"))
    )
    (net (code "110") (name "unconnected-(U1-PH1-OSC-OUT-Pad6)") (class "Default")
      (node (ref "U1") (pin "6") (pinfunction "PH1-OSC-OUT_6") (pintype "bidirectional"))
    )
  )
)
